# FOC_ESC_V1_0.net
KiCad netlist of a schematic drawn in Altium Designer
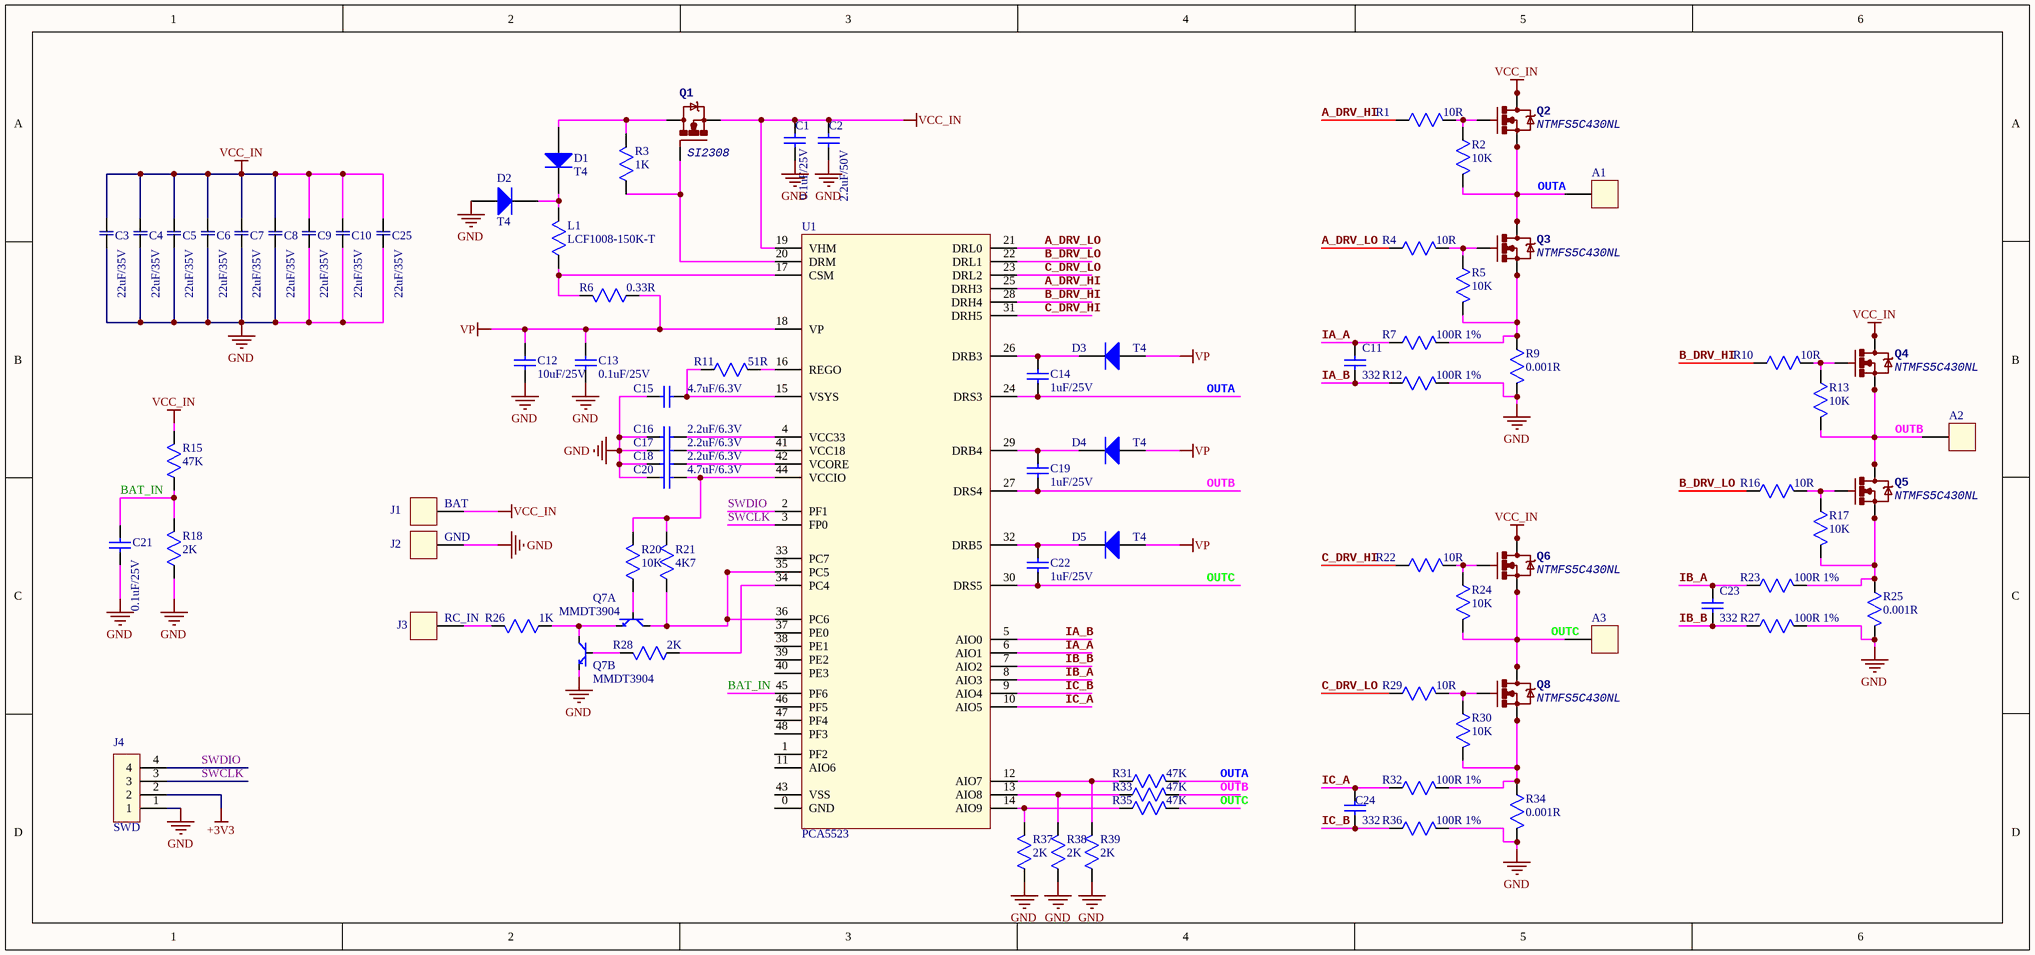
[diagram p0: FOC_ESC V1.0.SchDoc]

(export (version "E")
  (design (tool "Eeschema 10.0.6"))
  (components
    (comp (ref "A1") (value "~") (footprint "PAD-1  4*3") (libsource (lib "") (part "PAD_1")))
    (comp (ref "A2") (value "~") (footprint "PAD-1  4*3") (libsource (lib "") (part "PAD_1")))
    (comp (ref "A3") (value "~") (footprint "PAD-1  4*3") (libsource (lib "") (part "PAD_1")))
    (comp (ref "C1")
      (value "0.1uF/25V")
      (footprint "0603-RES")
      (fields (field (name "PUBLISHER") "Altium Limited"))
      (libsource (lib "DYS-XM30A V3.0") (part "Cap"))
    )
    (comp (ref "C2")
      (value "2.2uF/50V")
      (footprint "0805-RES")
      (fields (field (name "PUBLISHER") "Altium Limited"))
      (libsource (lib "DYS-XM30A V3.0") (part "Cap"))
    )
    (comp (ref "C3") (value "22uF/35V") (footprint "1206-RES") (libsource (lib "USER-2016") (part "C")))
    (comp (ref "C4") (value "22uF/35V") (footprint "1206-RES") (libsource (lib "USER-2016") (part "C")))
    (comp (ref "C5") (value "22uF/35V") (footprint "1206-RES") (libsource (lib "USER-2016") (part "C")))
    (comp (ref "C6") (value "22uF/35V") (footprint "1206-RES") (libsource (lib "USER-2016") (part "C")))
    (comp (ref "C7") (value "22uF/35V") (footprint "1206-RES") (libsource (lib "USER-2016") (part "C")))
    (comp (ref "C8") (value "22uF/35V") (footprint "1206-RES") (libsource (lib "USER-2016") (part "C")))
    (comp (ref "C9") (value "22uF/35V") (footprint "1206-RES") (libsource (lib "USER-2016") (part "C")))
    (comp (ref "C10") (value "22uF/35V") (footprint "1206-RES") (libsource (lib "USER-2016") (part "C")))
    (comp (ref "C11")
      (value "332")
      (footprint "0402-RES")
      (fields (field (name "PUBLISHER") "Altium Limited"))
      (libsource (lib "DYS-XM30A V3.0") (part "Cap"))
    )
    (comp (ref "C12")
      (value "10uF/25V")
      (footprint "0805-RES")
      (fields (field (name "PUBLISHER") "Altium Limited"))
      (libsource (lib "DYS-XM30A V3.0") (part "Cap"))
    )
    (comp (ref "C13")
      (value "0.1uF/25V")
      (footprint "0603-RES")
      (fields (field (name "PUBLISHER") "Altium Limited"))
      (libsource (lib "DYS-XM30A V3.0") (part "Cap"))
    )
    (comp (ref "C14")
      (value "1uF/25V")
      (footprint "0805-RES")
      (fields (field (name "PUBLISHER") "Altium Limited"))
      (libsource (lib "DYS-XM30A V3.0") (part "Cap"))
    )
    (comp (ref "C15")
      (value "4.7uF/6.3V")
      (footprint "0402-RES")
      (fields (field (name "PUBLISHER") "Altium Limited"))
      (libsource (lib "DYS-XM30A V3.0") (part "Cap"))
    )
    (comp (ref "C16")
      (value "2.2uF/6.3V")
      (footprint "0402-RES")
      (fields (field (name "PUBLISHER") "Altium Limited"))
      (libsource (lib "DYS-XM30A V3.0") (part "Cap"))
    )
    (comp (ref "C17")
      (value "2.2uF/6.3V")
      (footprint "0402-RES")
      (fields (field (name "PUBLISHER") "Altium Limited"))
      (libsource (lib "DYS-XM30A V3.0") (part "Cap"))
    )
    (comp (ref "C18")
      (value "2.2uF/6.3V")
      (footprint "0402-RES")
      (fields (field (name "PUBLISHER") "Altium Limited"))
      (libsource (lib "DYS-XM30A V3.0") (part "Cap"))
    )
    (comp (ref "C19")
      (value "1uF/25V")
      (footprint "0805-RES")
      (fields (field (name "PUBLISHER") "Altium Limited"))
      (libsource (lib "DYS-XM30A V3.0") (part "Cap"))
    )
    (comp (ref "C20")
      (value "4.7uF/6.3V")
      (footprint "0402-RES")
      (fields (field (name "PUBLISHER") "Altium Limited"))
      (libsource (lib "DYS-XM30A V3.0") (part "Cap"))
    )
    (comp (ref "C21")
      (value "0.1uF/25V")
      (footprint "0402-RES")
      (fields (field (name "PUBLISHER") "Altium Limited"))
      (libsource (lib "DYS-XM30A V3.0") (part "Cap"))
    )
    (comp (ref "C22")
      (value "1uF/25V")
      (footprint "0805-RES")
      (fields (field (name "PUBLISHER") "Altium Limited"))
      (libsource (lib "DYS-XM30A V3.0") (part "Cap"))
    )
    (comp (ref "C23")
      (value "332")
      (footprint "0402-RES")
      (fields (field (name "PUBLISHER") "Altium Limited"))
      (libsource (lib "DYS-XM30A V3.0") (part "Cap"))
    )
    (comp (ref "C24")
      (value "332")
      (footprint "0402-RES")
      (fields (field (name "PUBLISHER") "Altium Limited"))
      (libsource (lib "DYS-XM30A V3.0") (part "Cap"))
    )
    (comp (ref "C25") (value "22uF/35V") (footprint "1206-RES") (libsource (lib "USER-2016") (part "C")))
    (comp (ref "D1")
      (value "T4")
      (footprint "SOD323")
      (fields (field (name "PUBLISHER") "Altium Limited"))
      (libsource (lib "DYS-XM30A V3.0") (part "Diode"))
    )
    (comp (ref "D2")
      (value "T4")
      (footprint "SOD323")
      (fields (field (name "PUBLISHER") "Altium Limited"))
      (libsource (lib "DYS-XM30A V3.0") (part "Diode"))
    )
    (comp (ref "D3")
      (value "T4")
      (footprint "SOD323")
      (fields (field (name "PUBLISHER") "Altium Limited"))
      (libsource (lib "DYS-XM30A V3.0") (part "Diode"))
    )
    (comp (ref "D4")
      (value "T4")
      (footprint "SOD323")
      (fields (field (name "PUBLISHER") "Altium Limited"))
      (libsource (lib "DYS-XM30A V3.0") (part "Diode"))
    )
    (comp (ref "D5")
      (value "T4")
      (footprint "SOD323")
      (fields (field (name "PUBLISHER") "Altium Limited"))
      (libsource (lib "DYS-XM30A V3.0") (part "Diode"))
    )
    (comp (ref "J1") (value "BAT") (footprint "PAD-1  4*3") (libsource (lib "USER-2016") (part "PAD")))
    (comp (ref "J2") (value "GND") (footprint "PAD-1  4*3") (libsource (lib "USER-2016") (part "PAD")))
    (comp (ref "J3") (value "RC_IN") (footprint "PAD-1  2*1.5") (libsource (lib "USER-2016") (part "PAD")))
    (comp (ref "J4") (value "SWD") (footprint "1.0-4p") (libsource (lib "USER-2016") (part "J_4P")))
    (comp (ref "L1")
      (value "LCF1008-150K-T")
      (footprint "LCF1008-RES")
      (libsource (lib "USER-2016") (part "R"))
    )
    (comp (ref "Q1") (value "SI2308") (footprint "SOT-23") (libsource (lib "USER-2016") (part "P-MOS")))
    (comp (ref "Q2")
      (value "NTMFS5C430NL")
      (footprint "DFN5*6")
      (libsource (lib "USER-2016") (part "AON7418"))
    )
    (comp (ref "Q3")
      (value "NTMFS5C430NL")
      (footprint "DFN5*6")
      (libsource (lib "USER-2016") (part "AON7418"))
    )
    (comp (ref "Q4")
      (value "NTMFS5C430NL")
      (footprint "DFN5*6")
      (libsource (lib "USER-2016") (part "AON7418"))
    )
    (comp (ref "Q5")
      (value "NTMFS5C430NL")
      (footprint "DFN5*6")
      (libsource (lib "USER-2016") (part "AON7418"))
    )
    (comp (ref "Q6")
      (value "NTMFS5C430NL")
      (footprint "DFN5*6")
      (libsource (lib "USER-2016") (part "AON7418"))
    )
    (comp (ref "Q7") (value "MMDT3904") (footprint "SOC70-6") (libsource (lib "USER-2016") (part "MMDT3904")))
    (comp (ref "Q8")
      (value "NTMFS5C430NL")
      (footprint "DFN5*6")
      (libsource (lib "USER-2016") (part "AON7418"))
    )
    (comp (ref "R1") (value "10R") (footprint "0402-RES") (libsource (lib "USER-2016") (part "R")))
    (comp (ref "R2") (value "10K") (footprint "0402-RES") (libsource (lib "USER-2016") (part "R")))
    (comp (ref "R3") (value "1K") (footprint "0402-RES") (libsource (lib "USER-2016") (part "R")))
    (comp (ref "R4") (value "10R") (footprint "0402-RES") (libsource (lib "USER-2016") (part "R")))
    (comp (ref "R5") (value "10K") (footprint "0402-RES") (libsource (lib "USER-2016") (part "R")))
    (comp (ref "R6") (value "0.33R") (footprint "0805-RES") (libsource (lib "USER-2016") (part "R")))
    (comp (ref "R7") (value "100R 1%") (footprint "0402-RES") (libsource (lib "USER-2016") (part "R")))
    (comp (ref "R9") (value "0.001R") (footprint "2512-RES") (libsource (lib "USER-2016") (part "R")))
    (comp (ref "R10") (value "10R") (footprint "0402-RES") (libsource (lib "USER-2016") (part "R")))
    (comp (ref "R11") (value "51R") (footprint "0402-RES") (libsource (lib "USER-2016") (part "R")))
    (comp (ref "R12") (value "100R 1%") (footprint "0402-RES") (libsource (lib "USER-2016") (part "R")))
    (comp (ref "R13") (value "10K") (footprint "0402-RES") (libsource (lib "USER-2016") (part "R")))
    (comp (ref "R15") (value "47K") (footprint "0402-RES") (libsource (lib "USER-2016") (part "R")))
    (comp (ref "R16") (value "10R") (footprint "0402-RES") (libsource (lib "USER-2016") (part "R")))
    (comp (ref "R17") (value "10K") (footprint "0402-RES") (libsource (lib "USER-2016") (part "R")))
    (comp (ref "R18") (value "2K") (footprint "0402-RES") (libsource (lib "USER-2016") (part "R")))
    (comp (ref "R20") (value "10K") (footprint "0402-RES") (libsource (lib "USER-2016") (part "R")))
    (comp (ref "R21") (value "4K7") (footprint "0402-RES") (libsource (lib "USER-2016") (part "R")))
    (comp (ref "R22") (value "10R") (footprint "0402-RES") (libsource (lib "USER-2016") (part "R")))
    (comp (ref "R23") (value "100R 1%") (footprint "0402-RES") (libsource (lib "USER-2016") (part "R")))
    (comp (ref "R24") (value "10K") (footprint "0402-RES") (libsource (lib "USER-2016") (part "R")))
    (comp (ref "R25") (value "0.001R") (footprint "2512-RES") (libsource (lib "USER-2016") (part "R")))
    (comp (ref "R26") (value "1K") (footprint "0402-RES") (libsource (lib "USER-2016") (part "R")))
    (comp (ref "R27") (value "100R 1%") (footprint "0402-RES") (libsource (lib "USER-2016") (part "R")))
    (comp (ref "R28") (value "2K") (footprint "0402-RES") (libsource (lib "USER-2016") (part "R")))
    (comp (ref "R29") (value "10R") (footprint "0402-RES") (libsource (lib "USER-2016") (part "R")))
    (comp (ref "R30") (value "10K") (footprint "0402-RES") (libsource (lib "USER-2016") (part "R")))
    (comp (ref "R31") (value "47K") (footprint "0402-RES") (libsource (lib "USER-2016") (part "R")))
    (comp (ref "R32") (value "100R 1%") (footprint "0402-RES") (libsource (lib "USER-2016") (part "R")))
    (comp (ref "R33") (value "47K") (footprint "0402-RES") (libsource (lib "USER-2016") (part "R")))
    (comp (ref "R34") (value "0.001R") (footprint "2512-RES") (libsource (lib "USER-2016") (part "R")))
    (comp (ref "R35") (value "47K") (footprint "0402-RES") (libsource (lib "USER-2016") (part "R")))
    (comp (ref "R36") (value "100R 1%") (footprint "0402-RES") (libsource (lib "USER-2016") (part "R")))
    (comp (ref "R37") (value "2K") (footprint "0402-RES") (libsource (lib "USER-2016") (part "R")))
    (comp (ref "R38") (value "2K") (footprint "0402-RES") (libsource (lib "USER-2016") (part "R")))
    (comp (ref "R39") (value "2K") (footprint "0402-RES") (libsource (lib "USER-2016") (part "R")))
    (comp (ref "U1") (value "PCA5523") (footprint "QFN48") (libsource (lib "USER-2016") (part "PCA5523")))
  )
  (nets
    (net (code "1") (name "+3V3") (class "Default")
      (node (ref "J4") (pin "2") (pinfunction "2_2") (pintype "passive"))
    )
    (net (code "2") (name "/A_DRV_HI") (class "Default")
      (node (ref "R1") (pin "1") (pinfunction "1_1") (pintype "passive"))
      (node (ref "U1") (pin "25") (pinfunction "DRH3_25") (pintype "passive"))
    )
    (net (code "3") (name "/A_DRV_LO") (class "Default")
      (node (ref "R4") (pin "1") (pinfunction "1_1") (pintype "passive"))
      (node (ref "U1") (pin "21") (pinfunction "DRL0_21") (pintype "passive"))
    )
    (net (code "4") (name "/BAT_IN") (class "Default")
      (node (ref "C21") (pin "1") (pinfunction "1_1") (pintype "passive"))
      (node (ref "R15") (pin "1") (pinfunction "1_1") (pintype "passive"))
      (node (ref "R18") (pin "2") (pinfunction "2_2") (pintype "passive"))
      (node (ref "U1") (pin "45") (pinfunction "PF6_45") (pintype "passive"))
    )
    (net (code "5") (name "/B_DRV_HI") (class "Default")
      (node (ref "R10") (pin "1") (pinfunction "1_1") (pintype "passive"))
      (node (ref "U1") (pin "28") (pinfunction "DRH4_28") (pintype "passive"))
    )
    (net (code "6") (name "/B_DRV_LO") (class "Default")
      (node (ref "R16") (pin "1") (pinfunction "1_1") (pintype "passive"))
      (node (ref "U1") (pin "22") (pinfunction "DRL1_22") (pintype "passive"))
    )
    (net (code "7") (name "/C_DRV_HI") (class "Default")
      (node (ref "R22") (pin "1") (pinfunction "1_1") (pintype "passive"))
      (node (ref "U1") (pin "31") (pinfunction "DRH5_31") (pintype "passive"))
    )
    (net (code "8") (name "/C_DRV_LO") (class "Default")
      (node (ref "R29") (pin "1") (pinfunction "1_1") (pintype "passive"))
      (node (ref "U1") (pin "23") (pinfunction "DRL2_23") (pintype "passive"))
    )
    (net (code "9") (name "/IA_A") (class "Default")
      (node (ref "C11") (pin "1") (pinfunction "1_1") (pintype "passive"))
      (node (ref "R7") (pin "1") (pinfunction "1_1") (pintype "passive"))
      (node (ref "U1") (pin "6") (pinfunction "AIO1_6") (pintype "passive"))
    )
    (net (code "10") (name "/IA_B") (class "Default")
      (node (ref "C11") (pin "2") (pinfunction "2_2") (pintype "passive"))
      (node (ref "R12") (pin "1") (pinfunction "1_1") (pintype "passive"))
      (node (ref "U1") (pin "5") (pinfunction "AIO0_5") (pintype "passive"))
    )
    (net (code "11") (name "/IB_A") (class "Default")
      (node (ref "C23") (pin "1") (pinfunction "1_1") (pintype "passive"))
      (node (ref "R23") (pin "1") (pinfunction "1_1") (pintype "passive"))
      (node (ref "U1") (pin "8") (pinfunction "AIO3_8") (pintype "passive"))
    )
    (net (code "12") (name "/IB_B") (class "Default")
      (node (ref "C23") (pin "2") (pinfunction "2_2") (pintype "passive"))
      (node (ref "R27") (pin "1") (pinfunction "1_1") (pintype "passive"))
      (node (ref "U1") (pin "7") (pinfunction "AIO2_7") (pintype "passive"))
    )
    (net (code "13") (name "/IC_A") (class "Default")
      (node (ref "C24") (pin "1") (pinfunction "1_1") (pintype "passive"))
      (node (ref "R32") (pin "1") (pinfunction "1_1") (pintype "passive"))
      (node (ref "U1") (pin "10") (pinfunction "AIO5_10") (pintype "passive"))
    )
    (net (code "14") (name "/IC_B") (class "Default")
      (node (ref "C24") (pin "2") (pinfunction "2_2") (pintype "passive"))
      (node (ref "R36") (pin "1") (pinfunction "1_1") (pintype "passive"))
      (node (ref "U1") (pin "9") (pinfunction "AIO4_9") (pintype "passive"))
    )
    (net (code "15") (name "/OUTA") (class "Default")
      (node (ref "A1") (pin "1") (pinfunction "1_1") (pintype "passive"))
      (node (ref "C14") (pin "2") (pinfunction "2_2") (pintype "passive"))
      (node (ref "Q2") (pin "3") (pinfunction "S_3") (pintype "passive"))
      (node (ref "Q3") (pin "5") (pinfunction "D_5") (pintype "passive"))
      (node (ref "R2") (pin "2") (pinfunction "2_2") (pintype "passive"))
      (node (ref "R31") (pin "2") (pinfunction "2_2") (pintype "passive"))
      (node (ref "U1") (pin "24") (pinfunction "DRS3_24") (pintype "passive"))
    )
    (net (code "16") (name "/OUTB") (class "Default")
      (node (ref "A2") (pin "1") (pinfunction "1_1") (pintype "passive"))
      (node (ref "C19") (pin "2") (pinfunction "2_2") (pintype "passive"))
      (node (ref "Q4") (pin "3") (pinfunction "S_3") (pintype "passive"))
      (node (ref "Q5") (pin "5") (pinfunction "D_5") (pintype "passive"))
      (node (ref "R13") (pin "2") (pinfunction "2_2") (pintype "passive"))
      (node (ref "R33") (pin "2") (pinfunction "2_2") (pintype "passive"))
      (node (ref "U1") (pin "27") (pinfunction "DRS4_27") (pintype "passive"))
    )
    (net (code "17") (name "/OUTC") (class "Default")
      (node (ref "A3") (pin "1") (pinfunction "1_1") (pintype "passive"))
      (node (ref "C22") (pin "2") (pinfunction "2_2") (pintype "passive"))
      (node (ref "Q6") (pin "3") (pinfunction "S_3") (pintype "passive"))
      (node (ref "Q8") (pin "5") (pinfunction "D_5") (pintype "passive"))
      (node (ref "R24") (pin "2") (pinfunction "2_2") (pintype "passive"))
      (node (ref "R35") (pin "2") (pinfunction "2_2") (pintype "passive"))
      (node (ref "U1") (pin "30") (pinfunction "DRS5_30") (pintype "passive"))
    )
    (net (code "18") (name "/SWCLK") (class "Default")
      (node (ref "J4") (pin "3") (pinfunction "3_3") (pintype "passive"))
      (node (ref "U1") (pin "3") (pinfunction "FP0_3") (pintype "passive"))
    )
    (net (code "19") (name "/SWDIO") (class "Default")
      (node (ref "J4") (pin "4") (pinfunction "4_4") (pintype "passive"))
      (node (ref "U1") (pin "2") (pinfunction "PF1_2") (pintype "passive"))
    )
    (net (code "20") (name "GND") (class "Default")
      (node (ref "C1") (pin "2") (pinfunction "2_2") (pintype "passive"))
      (node (ref "C10") (pin "2") (pinfunction "2_2") (pintype "passive"))
      (node (ref "C12") (pin "2") (pinfunction "2_2") (pintype "passive"))
      (node (ref "C13") (pin "2") (pinfunction "2_2") (pintype "passive"))
      (node (ref "C15") (pin "1") (pinfunction "1_1") (pintype "passive"))
      (node (ref "C16") (pin "1") (pinfunction "1_1") (pintype "passive"))
      (node (ref "C17") (pin "1") (pinfunction "1_1") (pintype "passive"))
      (node (ref "C18") (pin "1") (pinfunction "1_1") (pintype "passive"))
      (node (ref "C2") (pin "2") (pinfunction "2_2") (pintype "passive"))
      (node (ref "C20") (pin "1") (pinfunction "1_1") (pintype "passive"))
      (node (ref "C21") (pin "2") (pinfunction "2_2") (pintype "passive"))
      (node (ref "C25") (pin "2") (pinfunction "2_2") (pintype "passive"))
      (node (ref "C3") (pin "2") (pinfunction "2_2") (pintype "passive"))
      (node (ref "C4") (pin "2") (pinfunction "2_2") (pintype "passive"))
      (node (ref "C5") (pin "2") (pinfunction "2_2") (pintype "passive"))
      (node (ref "C6") (pin "2") (pinfunction "2_2") (pintype "passive"))
      (node (ref "C7") (pin "2") (pinfunction "2_2") (pintype "passive"))
      (node (ref "C8") (pin "2") (pinfunction "2_2") (pintype "passive"))
      (node (ref "C9") (pin "2") (pinfunction "2_2") (pintype "passive"))
      (node (ref "D2") (pin "1") (pinfunction "A_1") (pintype "passive"))
      (node (ref "J2") (pin "1") (pinfunction "1_1") (pintype "passive"))
      (node (ref "J4") (pin "1") (pinfunction "1_1") (pintype "passive"))
      (node (ref "Q7") (pin "4") (pinfunction "E_4") (pintype "passive"))
      (node (ref "R12") (pin "2") (pinfunction "2_2") (pintype "passive"))
      (node (ref "R18") (pin "1") (pinfunction "1_1") (pintype "passive"))
      (node (ref "R25") (pin "2") (pinfunction "2_2") (pintype "passive"))
      (node (ref "R27") (pin "2") (pinfunction "2_2") (pintype "passive"))
      (node (ref "R34") (pin "2") (pinfunction "2_2") (pintype "passive"))
      (node (ref "R36") (pin "2") (pinfunction "2_2") (pintype "passive"))
      (node (ref "R37") (pin "1") (pinfunction "1_1") (pintype "passive"))
      (node (ref "R38") (pin "1") (pinfunction "1_1") (pintype "passive"))
      (node (ref "R39") (pin "1") (pinfunction "1_1") (pintype "passive"))
      (node (ref "R9") (pin "2") (pinfunction "2_2") (pintype "passive"))
    )
    (net (code "21") (name "Net-(D1-A)") (class "Default")
      (node (ref "D1") (pin "1") (pinfunction "A_1") (pintype "passive"))
      (node (ref "Q1") (pin "3") (pinfunction "D_3") (pintype "passive"))
      (node (ref "R3") (pin "2") (pinfunction "2_2") (pintype "passive"))
    )
    (net (code "22") (name "Net-(D1-K)") (class "Default")
      (node (ref "D1") (pin "2") (pinfunction "K_2") (pintype "passive"))
      (node (ref "D2") (pin "2") (pinfunction "K_2") (pintype "passive"))
      (node (ref "L1") (pin "2") (pinfunction "2_2") (pintype "passive"))
    )
    (net (code "23") (name "Net-(D3-K)") (class "Default")
      (node (ref "C14") (pin "1") (pinfunction "1_1") (pintype "passive"))
      (node (ref "D3") (pin "2") (pinfunction "K_2") (pintype "passive"))
      (node (ref "U1") (pin "26") (pinfunction "DRB3_26") (pintype "passive"))
    )
    (net (code "24") (name "Net-(D4-K)") (class "Default")
      (node (ref "C19") (pin "1") (pinfunction "1_1") (pintype "passive"))
      (node (ref "D4") (pin "2") (pinfunction "K_2") (pintype "passive"))
      (node (ref "U1") (pin "29") (pinfunction "DRB4_29") (pintype "passive"))
    )
    (net (code "25") (name "Net-(D5-K)") (class "Default")
      (node (ref "C22") (pin "1") (pinfunction "1_1") (pintype "passive"))
      (node (ref "D5") (pin "2") (pinfunction "K_2") (pintype "passive"))
      (node (ref "U1") (pin "32") (pinfunction "DRB5_32") (pintype "passive"))
    )
    (net (code "26") (name "Net-(J3-Pad1)") (class "Default")
      (node (ref "J3") (pin "1") (pinfunction "1_1") (pintype "passive"))
      (node (ref "R26") (pin "2") (pinfunction "2_2") (pintype "passive"))
    )
    (net (code "27") (name "Net-(Q1-G)") (class "Default")
      (node (ref "Q1") (pin "1") (pinfunction "G_1") (pintype "passive"))
      (node (ref "R3") (pin "1") (pinfunction "1_1") (pintype "passive"))
      (node (ref "U1") (pin "20") (pinfunction "DRM_20") (pintype "passive"))
    )
    (net (code "28") (name "Net-(Q2-G)") (class "Default")
      (node (ref "Q2") (pin "4") (pinfunction "G_4") (pintype "passive"))
      (node (ref "R1") (pin "2") (pinfunction "2_2") (pintype "passive"))
      (node (ref "R2") (pin "1") (pinfunction "1_1") (pintype "passive"))
    )
    (net (code "29") (name "Net-(Q3-G)") (class "Default")
      (node (ref "Q3") (pin "4") (pinfunction "G_4") (pintype "passive"))
      (node (ref "R4") (pin "2") (pinfunction "2_2") (pintype "passive"))
      (node (ref "R5") (pin "1") (pinfunction "1_1") (pintype "passive"))
    )
    (net (code "30") (name "Net-(Q3-S)") (class "Default")
      (node (ref "Q3") (pin "3") (pinfunction "S_3") (pintype "passive"))
      (node (ref "R5") (pin "2") (pinfunction "2_2") (pintype "passive"))
      (node (ref "R7") (pin "2") (pinfunction "2_2") (pintype "passive"))
      (node (ref "R9") (pin "1") (pinfunction "1_1") (pintype "passive"))
    )
    (net (code "31") (name "Net-(Q4-G)") (class "Default")
      (node (ref "Q4") (pin "4") (pinfunction "G_4") (pintype "passive"))
      (node (ref "R10") (pin "2") (pinfunction "2_2") (pintype "passive"))
      (node (ref "R13") (pin "1") (pinfunction "1_1") (pintype "passive"))
    )
    (net (code "32") (name "Net-(Q5-G)") (class "Default")
      (node (ref "Q5") (pin "4") (pinfunction "G_4") (pintype "passive"))
      (node (ref "R16") (pin "2") (pinfunction "2_2") (pintype "passive"))
      (node (ref "R17") (pin "1") (pinfunction "1_1") (pintype "passive"))
    )
    (net (code "33") (name "Net-(Q5-S)") (class "Default")
      (node (ref "Q5") (pin "3") (pinfunction "S_3") (pintype "passive"))
      (node (ref "R17") (pin "2") (pinfunction "2_2") (pintype "passive"))
      (node (ref "R23") (pin "2") (pinfunction "2_2") (pintype "passive"))
      (node (ref "R25") (pin "1") (pinfunction "1_1") (pintype "passive"))
    )
    (net (code "34") (name "Net-(Q6-G)") (class "Default")
      (node (ref "Q6") (pin "4") (pinfunction "G_4") (pintype "passive"))
      (node (ref "R22") (pin "2") (pinfunction "2_2") (pintype "passive"))
      (node (ref "R24") (pin "1") (pinfunction "1_1") (pintype "passive"))
    )
    (net (code "35") (name "Net-(Q7A-B)") (class "Default")
      (node (ref "Q7") (pin "2") (pinfunction "B_2") (pintype "passive"))
      (node (ref "R20") (pin "1") (pinfunction "1_1") (pintype "passive"))
    )
    (net (code "36") (name "Net-(Q7A-C)") (class "Default")
      (node (ref "Q7") (pin "6") (pinfunction "C_6") (pintype "passive"))
      (node (ref "R21") (pin "1") (pinfunction "1_1") (pintype "passive"))
      (node (ref "U1") (pin "35") (pinfunction "PC5_35") (pintype "passive"))
      (node (ref "U1") (pin "36") (pinfunction "PC6_36") (pintype "passive"))
    )
    (net (code "37") (name "Net-(Q7A-E)") (class "Default")
      (node (ref "Q7") (pin "1") (pinfunction "E_1") (pintype "passive"))
      (node (ref "Q7") (pin "3") (pinfunction "C_3") (pintype "passive"))
      (node (ref "R26") (pin "1") (pinfunction "1_1") (pintype "passive"))
    )
    (net (code "38") (name "Net-(Q7B-B)") (class "Default")
      (node (ref "Q7") (pin "5") (pinfunction "B_5") (pintype "passive"))
      (node (ref "R28") (pin "2") (pinfunction "2_2") (pintype "passive"))
    )
    (net (code "39") (name "Net-(Q8-G)") (class "Default")
      (node (ref "Q8") (pin "4") (pinfunction "G_4") (pintype "passive"))
      (node (ref "R29") (pin "2") (pinfunction "2_2") (pintype "passive"))
      (node (ref "R30") (pin "1") (pinfunction "1_1") (pintype "passive"))
    )
    (net (code "40") (name "Net-(Q8-S)") (class "Default")
      (node (ref "Q8") (pin "3") (pinfunction "S_3") (pintype "passive"))
      (node (ref "R30") (pin "2") (pinfunction "2_2") (pintype "passive"))
      (node (ref "R32") (pin "2") (pinfunction "2_2") (pintype "passive"))
      (node (ref "R34") (pin "1") (pinfunction "1_1") (pintype "passive"))
    )
    (net (code "41") (name "Net-(U1-AIO7)") (class "Default")
      (node (ref "R31") (pin "1") (pinfunction "1_1") (pintype "passive"))
      (node (ref "R39") (pin "2") (pinfunction "2_2") (pintype "passive"))
      (node (ref "U1") (pin "12") (pinfunction "AIO7_12") (pintype "passive"))
    )
    (net (code "42") (name "Net-(U1-AIO8)") (class "Default")
      (node (ref "R33") (pin "1") (pinfunction "1_1") (pintype "passive"))
      (node (ref "R38") (pin "2") (pinfunction "2_2") (pintype "passive"))
      (node (ref "U1") (pin "13") (pinfunction "AIO8_13") (pintype "passive"))
    )
    (net (code "43") (name "Net-(U1-AIO9)") (class "Default")
      (node (ref "R35") (pin "1") (pinfunction "1_1") (pintype "passive"))
      (node (ref "R37") (pin "2") (pinfunction "2_2") (pintype "passive"))
      (node (ref "U1") (pin "14") (pinfunction "AIO9_14") (pintype "passive"))
    )
    (net (code "44") (name "Net-(U1-CSM)") (class "Default")
      (node (ref "L1") (pin "1") (pinfunction "1_1") (pintype "passive"))
      (node (ref "R6") (pin "2") (pinfunction "2_2") (pintype "passive"))
      (node (ref "U1") (pin "17") (pinfunction "CSM_17") (pintype "passive"))
    )
    (net (code "45") (name "Net-(U1-PC4)") (class "Default")
      (node (ref "R28") (pin "1") (pinfunction "1_1") (pintype "passive"))
      (node (ref "U1") (pin "34") (pinfunction "PC4_34") (pintype "passive"))
    )
    (net (code "46") (name "Net-(U1-REGO)") (class "Default")
      (node (ref "R11") (pin "2") (pinfunction "2_2") (pintype "passive"))
      (node (ref "U1") (pin "16") (pinfunction "REGO_16") (pintype "passive"))
    )
    (net (code "47") (name "Net-(U1-VCC18)") (class "Default")
      (node (ref "C17") (pin "2") (pinfunction "2_2") (pintype "passive"))
      (node (ref "U1") (pin "41") (pinfunction "VCC18_41") (pintype "passive"))
    )
    (net (code "48") (name "Net-(U1-VCC33)") (class "Default")
      (node (ref "C16") (pin "2") (pinfunction "2_2") (pintype "passive"))
      (node (ref "U1") (pin "4") (pinfunction "VCC33_4") (pintype "passive"))
    )
    (net (code "49") (name "Net-(U1-VCCIO)") (class "Default")
      (node (ref "C20") (pin "2") (pinfunction "2_2") (pintype "passive"))
      (node (ref "R20") (pin "2") (pinfunction "2_2") (pintype "passive"))
      (node (ref "R21") (pin "2") (pinfunction "2_2") (pintype "passive"))
      (node (ref "U1") (pin "44") (pinfunction "VCCIO_44") (pintype "passive"))
    )
    (net (code "50") (name "Net-(U1-VCORE)") (class "Default")
      (node (ref "C18") (pin "2") (pinfunction "2_2") (pintype "passive"))
      (node (ref "U1") (pin "42") (pinfunction "VCORE_42") (pintype "passive"))
    )
    (net (code "51") (name "Net-(U1-VSYS)") (class "Default")
      (node (ref "C15") (pin "2") (pinfunction "2_2") (pintype "passive"))
      (node (ref "R11") (pin "1") (pinfunction "1_1") (pintype "passive"))
      (node (ref "U1") (pin "15") (pinfunction "VSYS_15") (pintype "passive"))
    )
    (net (code "52") (name "VCC_IN") (class "Default")
      (node (ref "C1") (pin "1") (pinfunction "1_1") (pintype "passive"))
      (node (ref "C10") (pin "1") (pinfunction "1_1") (pintype "passive"))
      (node (ref "C2") (pin "1") (pinfunction "1_1") (pintype "passive"))
      (node (ref "C25") (pin "1") (pinfunction "1_1") (pintype "passive"))
      (node (ref "C3") (pin "1") (pinfunction "1_1") (pintype "passive"))
      (node (ref "C4") (pin "1") (pinfunction "1_1") (pintype "passive"))
      (node (ref "C5") (pin "1") (pinfunction "1_1") (pintype "passive"))
      (node (ref "C6") (pin "1") (pinfunction "1_1") (pintype "passive"))
      (node (ref "C7") (pin "1") (pinfunction "1_1") (pintype "passive"))
      (node (ref "C8") (pin "1") (pinfunction "1_1") (pintype "passive"))
      (node (ref "C9") (pin "1") (pinfunction "1_1") (pintype "passive"))
      (node (ref "J1") (pin "1") (pinfunction "1_1") (pintype "passive"))
      (node (ref "Q1") (pin "2") (pinfunction "S_2") (pintype "passive"))
      (node (ref "Q2") (pin "5") (pinfunction "D_5") (pintype "passive"))
      (node (ref "Q4") (pin "5") (pinfunction "D_5") (pintype "passive"))
      (node (ref "Q6") (pin "5") (pinfunction "D_5") (pintype "passive"))
      (node (ref "R15") (pin "2") (pinfunction "2_2") (pintype "passive"))
      (node (ref "U1") (pin "19") (pinfunction "VHM_19") (pintype "passive"))
    )
    (net (code "53") (name "VP") (class "Default")
      (node (ref "C12") (pin "1") (pinfunction "1_1") (pintype "passive"))
      (node (ref "C13") (pin "1") (pinfunction "1_1") (pintype "passive"))
      (node (ref "D3") (pin "1") (pinfunction "A_1") (pintype "passive"))
      (node (ref "D4") (pin "1") (pinfunction "A_1") (pintype "passive"))
      (node (ref "D5") (pin "1") (pinfunction "A_1") (pintype "passive"))
      (node (ref "R6") (pin "1") (pinfunction "1_1") (pintype "passive"))
      (node (ref "U1") (pin "18") (pinfunction "VP_18") (pintype "passive"))
    )
    (net (code "54") (name "unconnected-(J4-GND-Pad0)") (class "Default")
      (node (ref "J4") (pin "0") (pinfunction "GND_0") (pintype "power_in"))
    )
    (net (code "55") (name "unconnected-(U1-AIO6-Pad11)") (class "Default")
      (node (ref "U1") (pin "11") (pinfunction "AIO6_11") (pintype "passive"))
    )
    (net (code "56") (name "unconnected-(U1-GND-Pad0)") (class "Default")
      (node (ref "U1") (pin "0") (pinfunction "GND_0") (pintype "passive"))
    )
    (net (code "57") (name "unconnected-(U1-PC7-Pad33)") (class "Default")
      (node (ref "U1") (pin "33") (pinfunction "PC7_33") (pintype "passive"))
    )
    (net (code "58") (name "unconnected-(U1-PE0-Pad37)") (class "Default")
      (node (ref "U1") (pin "37") (pinfunction "PE0_37") (pintype "passive"))
    )
    (net (code "59") (name "unconnected-(U1-PE1-Pad38)") (class "Default")
      (node (ref "U1") (pin "38") (pinfunction "PE1_38") (pintype "passive"))
    )
    (net (code "60") (name "unconnected-(U1-PE2-Pad39)") (class "Default")
      (node (ref "U1") (pin "39") (pinfunction "PE2_39") (pintype "passive"))
    )
    (net (code "61") (name "unconnected-(U1-PE3-Pad40)") (class "Default")
      (node (ref "U1") (pin "40") (pinfunction "PE3_40") (pintype "passive"))
    )
    (net (code "62") (name "unconnected-(U1-PF2-Pad1)") (class "Default")
      (node (ref "U1") (pin "1") (pinfunction "PF2_1") (pintype "passive"))
    )
    (net (code "63") (name "unconnected-(U1-PF3-Pad48)") (class "Default")
      (node (ref "U1") (pin "48") (pinfunction "PF3_48") (pintype "passive"))
    )
    (net (code "64") (name "unconnected-(U1-PF4-Pad47)") (class "Default")
      (node (ref "U1") (pin "47") (pinfunction "PF4_47") (pintype "passive"))
    )
    (net (code "65") (name "unconnected-(U1-PF5-Pad46)") (class "Default")
      (node (ref "U1") (pin "46") (pinfunction "PF5_46") (pintype "passive"))
    )
    (net (code "66") (name "unconnected-(U1-VSS-Pad43)") (class "Default")
      (node (ref "U1") (pin "43") (pinfunction "VSS_43") (pintype "passive"))
    )
  )
)
